# Actuators.net
KiCad netlist of a schematic drawn in Altium Designer
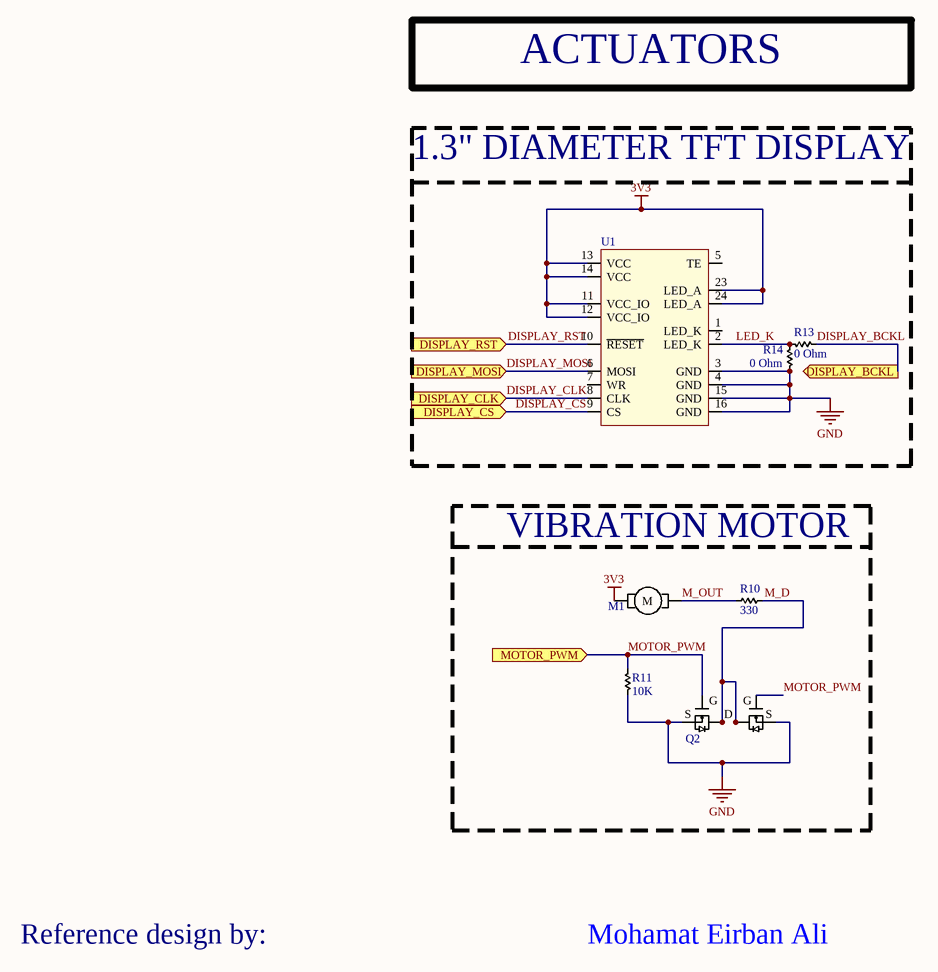
[diagram p0: Actuators.SchDoc]

(export (version "E")
  (design (tool "Eeschema 10.0.6"))
  (components
    (comp (ref "M1")
      (value "~")
      (footprint "C0720B001F")
      (description "DC Motor Vibration, ERM 10000 RPM 3VDC")
      (libsource (lib "smarchWatch_V5") (part "C0720B001F"))
    )
    (comp (ref "Q2")
      (value "~")
      (footprint "ECH8693R-TL-W")
      (description "Mosfet Array 2 N-Channel (Dual) Common Drain 24V 14A 1.4W Surface Mount SOT-28FL/ECH8")
      (libsource (lib "smarchWatch_V5") (part "ECH8693R-TL-W"))
    )
    (comp (ref "R10")
      (value "330")
      (footprint "RES_0603_HIGH")
      (description "0603 Resistor")
      (libsource (lib "smarchWatch_V5") (part "Resistor_0603_2"))
    )
    (comp (ref "R11")
      (value "10K")
      (footprint "RES_0603_HIGH")
      (description "0603 Resistor")
      (libsource (lib "smarchWatch_V5") (part "Resistor_0603_3"))
    )
    (comp (ref "R13")
      (value "0 Ohm")
      (footprint "RES_0603_HIGH")
      (description "0603 Resistor")
      (libsource (lib "smarchWatch_V5") (part "Resistor_0603_5"))
    )
    (comp (ref "R14")
      (value "0 Ohm")
      (footprint "RES_0603_HIGH")
      (description "0603 Resistor")
      (libsource (lib "smarchWatch_V5") (part "Resistor_0603_5"))
    )
    (comp (ref "U1")
      (value "~")
      (footprint "AML130A2402A")
      (description "AML130A2402A Round 1.3\" TFT Display")
      (libsource (lib "smarchWatch_V5") (part "AML130A2402A"))
    )
  )
  (nets
    (net (code "1") (name "/DISPLAY_BCKL") (class "Default")
      (node (ref "R13") (pin "1") (pinfunction "1_1") (pintype "passive"))
    )
    (net (code "2") (name "/DISPLAY_CLK") (class "Default")
      (node (ref "U1") (pin "8") (pinfunction "CLK_8") (pintype "passive"))
    )
    (net (code "3") (name "/DISPLAY_CS") (class "Default")
      (node (ref "U1") (pin "9") (pinfunction "CS_9") (pintype "passive"))
    )
    (net (code "4") (name "/DISPLAY_MOSI") (class "Default")
      (node (ref "U1") (pin "6") (pinfunction "MOSI_6") (pintype "passive"))
    )
    (net (code "5") (name "/DISPLAY_RST") (class "Default")
      (node (ref "U1") (pin "10") (pinfunction "~{RESET}_10") (pintype "passive"))
    )
    (net (code "6") (name "/LED_K") (class "Default")
      (node (ref "R13") (pin "2") (pinfunction "2_2") (pintype "passive"))
      (node (ref "R14") (pin "1") (pinfunction "1_1") (pintype "passive"))
      (node (ref "U1") (pin "2") (pinfunction "LED_K_2") (pintype "passive"))
    )
    (net (code "7") (name "/MOTOR_PWM") (class "Default")
      (node (ref "Q2") (pin "2") (pinfunction "G1_2") (pintype "passive"))
      (node (ref "Q2") (pin "4") (pinfunction "G2_4") (pintype "passive"))
      (node (ref "R11") (pin "2") (pinfunction "2_2") (pintype "passive"))
    )
    (net (code "8") (name "/M_D") (class "Default")
      (node (ref "Q2") (pin "5") (pinfunction "D_5") (pintype "passive"))
      (node (ref "Q2") (pin "6") (pinfunction "D_6") (pintype "passive"))
      (node (ref "Q2") (pin "7") (pinfunction "D_7") (pintype "passive"))
      (node (ref "Q2") (pin "8") (pinfunction "D_8") (pintype "passive"))
      (node (ref "R10") (pin "2") (pinfunction "2_2") (pintype "passive"))
    )
    (net (code "9") (name "/M_OUT") (class "Default")
      (node (ref "M1") (pin "2") (pinfunction "2_2") (pintype "passive"))
      (node (ref "R10") (pin "1") (pinfunction "1_1") (pintype "passive"))
    )
    (net (code "10") (name "3V3") (class "Default")
      (node (ref "M1") (pin "1") (pinfunction "1_1") (pintype "passive"))
      (node (ref "U1") (pin "11") (pinfunction "VCC_IO_11") (pintype "passive"))
      (node (ref "U1") (pin "12") (pinfunction "VCC_IO_12") (pintype "passive"))
      (node (ref "U1") (pin "13") (pinfunction "VCC_13") (pintype "passive"))
      (node (ref "U1") (pin "14") (pinfunction "VCC_14") (pintype "passive"))
      (node (ref "U1") (pin "23") (pinfunction "LED_A_23") (pintype "passive"))
      (node (ref "U1") (pin "24") (pinfunction "LED_A_24") (pintype "passive"))
    )
    (net (code "11") (name "GND") (class "Default")
      (node (ref "Q2") (pin "1") (pinfunction "S1_1") (pintype "passive"))
      (node (ref "Q2") (pin "3") (pinfunction "S2_3") (pintype "passive"))
      (node (ref "R11") (pin "1") (pinfunction "1_1") (pintype "passive"))
      (node (ref "R14") (pin "2") (pinfunction "2_2") (pintype "passive"))
      (node (ref "U1") (pin "15") (pinfunction "GND_15") (pintype "passive"))
      (node (ref "U1") (pin "16") (pinfunction "GND_16") (pintype "passive"))
      (node (ref "U1") (pin "3") (pinfunction "GND_3") (pintype "passive"))
      (node (ref "U1") (pin "4") (pinfunction "GND_4") (pintype "passive"))
    )
    (net (code "12") (name "unconnected-(U1-LED_K-Pad1)") (class "Default")
      (node (ref "U1") (pin "1") (pinfunction "LED_K_1") (pintype "passive"))
    )
    (net (code "13") (name "unconnected-(U1-TE-Pad5)") (class "Default")
      (node (ref "U1") (pin "5") (pinfunction "TE_5") (pintype "passive"))
    )
    (net (code "14") (name "unconnected-(U1-WR-Pad7)") (class "Default")
      (node (ref "U1") (pin "7") (pinfunction "WR_7") (pintype "passive"))
    )
  )
)
